# RV09-S_SCH.net
KiCad netlist of a schematic drawn in Altium Designer
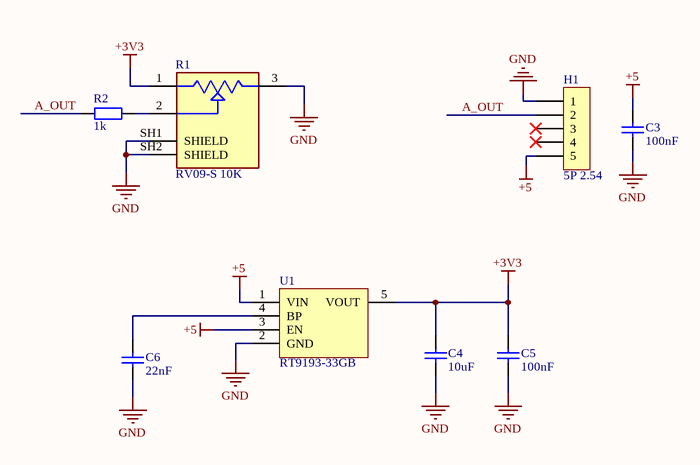
[diagram p0: RV09-S_SCH.SchDoc]

(export (version "E")
  (design (tool "Eeschema 10.0.6"))
  (components
    (comp (ref "C3")
      (value "100nF")
      (footprint "tu 0603")
      (description "Dán")
      (libsource (lib "namnt_Lib") (part "Tu 0603 104 50V 10%"))
    )
    (comp (ref "C4")
      (value "10uF")
      (footprint "tu 0603")
      (description "Dán")
      (libsource (lib "namnt_Lib") (part "Tu 0603 106 16V 20%"))
    )
    (comp (ref "C5")
      (value "100nF")
      (footprint "tu 0603")
      (description "Dán")
      (libsource (lib "namnt_Lib") (part "Tu 0603 104 50V 10%"))
    )
    (comp (ref "C6")
      (value "22nF")
      (footprint "tu 0603")
      (description "Dán")
      (libsource (lib "namnt_Lib") (part "Tu 0603 104 50V 10%"))
    )
    (comp (ref "H1")
      (value "5P 2.54")
      (footprint "Header 5P DC 2.54")
      (description "Cắm")
      (libsource (lib "namnt_Lib") (part "Header 5P 2.54 Duc Cong"))
    )
    (comp (ref "R1")
      (value "RV09-S 10K")
      (footprint "TRIM_RV09AF-40-20K-A10K")
      (fields (field (name "MF") "Alpha Taiwan") (field (name "MP") "RV09AF-40-20K-A10K"))
      (libsource (lib "namnt_Lib") (part "RV09-S 10k"))
    )
    (comp (ref "R2")
      (value "1k")
      (footprint "tro smd 0603")
      (description "Dán")
      (libsource (lib "namnt_Lib") (part "Tro 0603 1% 10k"))
    )
    (comp (ref "U1")
      (value "RT9193-33GB")
      (footprint "SOT23-5")
      (description "Linear Voltage Regulator IC 1 Output 300mA SOT-23-5")
      (fields (field (name "MANUFACTURER") "Richtek USA Inc."))
      (libsource (lib "namnt_Lib") (part "REG_5.5V-3.3V-0.3A-1W-SOT-23-5"))
    )
  )
  (nets
    (net (code "1") (name "+3V3") (class "Default")
      (node (ref "C4") (pin "1") (pinfunction "1_1") (pintype "passive"))
      (node (ref "C5") (pin "1") (pinfunction "1_1") (pintype "passive"))
      (node (ref "R1") (pin "1") (pinfunction "1_1") (pintype "passive"))
      (node (ref "U1") (pin "5") (pinfunction "VOUT_5") (pintype "passive"))
    )
    (net (code "2") (name "+5") (class "Default")
      (node (ref "C3") (pin "1") (pinfunction "1_1") (pintype "passive"))
      (node (ref "H1") (pin "5") (pinfunction "5_5") (pintype "passive"))
      (node (ref "U1") (pin "1") (pinfunction "VIN_1") (pintype "passive"))
      (node (ref "U1") (pin "3") (pinfunction "EN_3") (pintype "passive"))
    )
    (net (code "3") (name "/A_OUT") (class "Default")
      (node (ref "H1") (pin "2") (pinfunction "2_2") (pintype "passive"))
      (node (ref "R2") (pin "2") (pinfunction "2_2") (pintype "passive"))
    )
    (net (code "4") (name "GND") (class "Default")
      (node (ref "C3") (pin "2") (pinfunction "2_2") (pintype "passive"))
      (node (ref "C4") (pin "2") (pinfunction "2_2") (pintype "passive"))
      (node (ref "C5") (pin "2") (pinfunction "2_2") (pintype "passive"))
      (node (ref "C6") (pin "2") (pinfunction "2_2") (pintype "passive"))
      (node (ref "H1") (pin "1") (pinfunction "1_1") (pintype "passive"))
      (node (ref "R1") (pin "3") (pinfunction "3_3") (pintype "passive"))
      (node (ref "R1") (pin "SH1") (pinfunction "SHIELD_SH1") (pintype "passive"))
      (node (ref "R1") (pin "SH2") (pinfunction "SHIELD_SH2") (pintype "passive"))
      (node (ref "U1") (pin "2") (pinfunction "GND_2") (pintype "passive"))
    )
    (net (code "5") (name "Net-(R1-Pad2)") (class "Default")
      (node (ref "R1") (pin "2") (pinfunction "2_2") (pintype "passive"))
      (node (ref "R2") (pin "1") (pinfunction "1_1") (pintype "passive"))
    )
    (net (code "6") (name "Net-(U1-BP)") (class "Default")
      (node (ref "C6") (pin "1") (pinfunction "1_1") (pintype "passive"))
      (node (ref "U1") (pin "4") (pinfunction "BP_4") (pintype "passive"))
    )
    (net (code "7") (name "unconnected-(H1-Pad3)") (class "Default")
      (node (ref "H1") (pin "3") (pinfunction "3_3") (pintype "passive+no_connect"))
    )
    (net (code "8") (name "unconnected-(H1-Pad4)") (class "Default")
      (node (ref "H1") (pin "4") (pinfunction "4_4") (pintype "passive+no_connect"))
    )
  )
)
